# Telemetry_System.net
KiCad netlist of a schematic drawn in Altium Designer
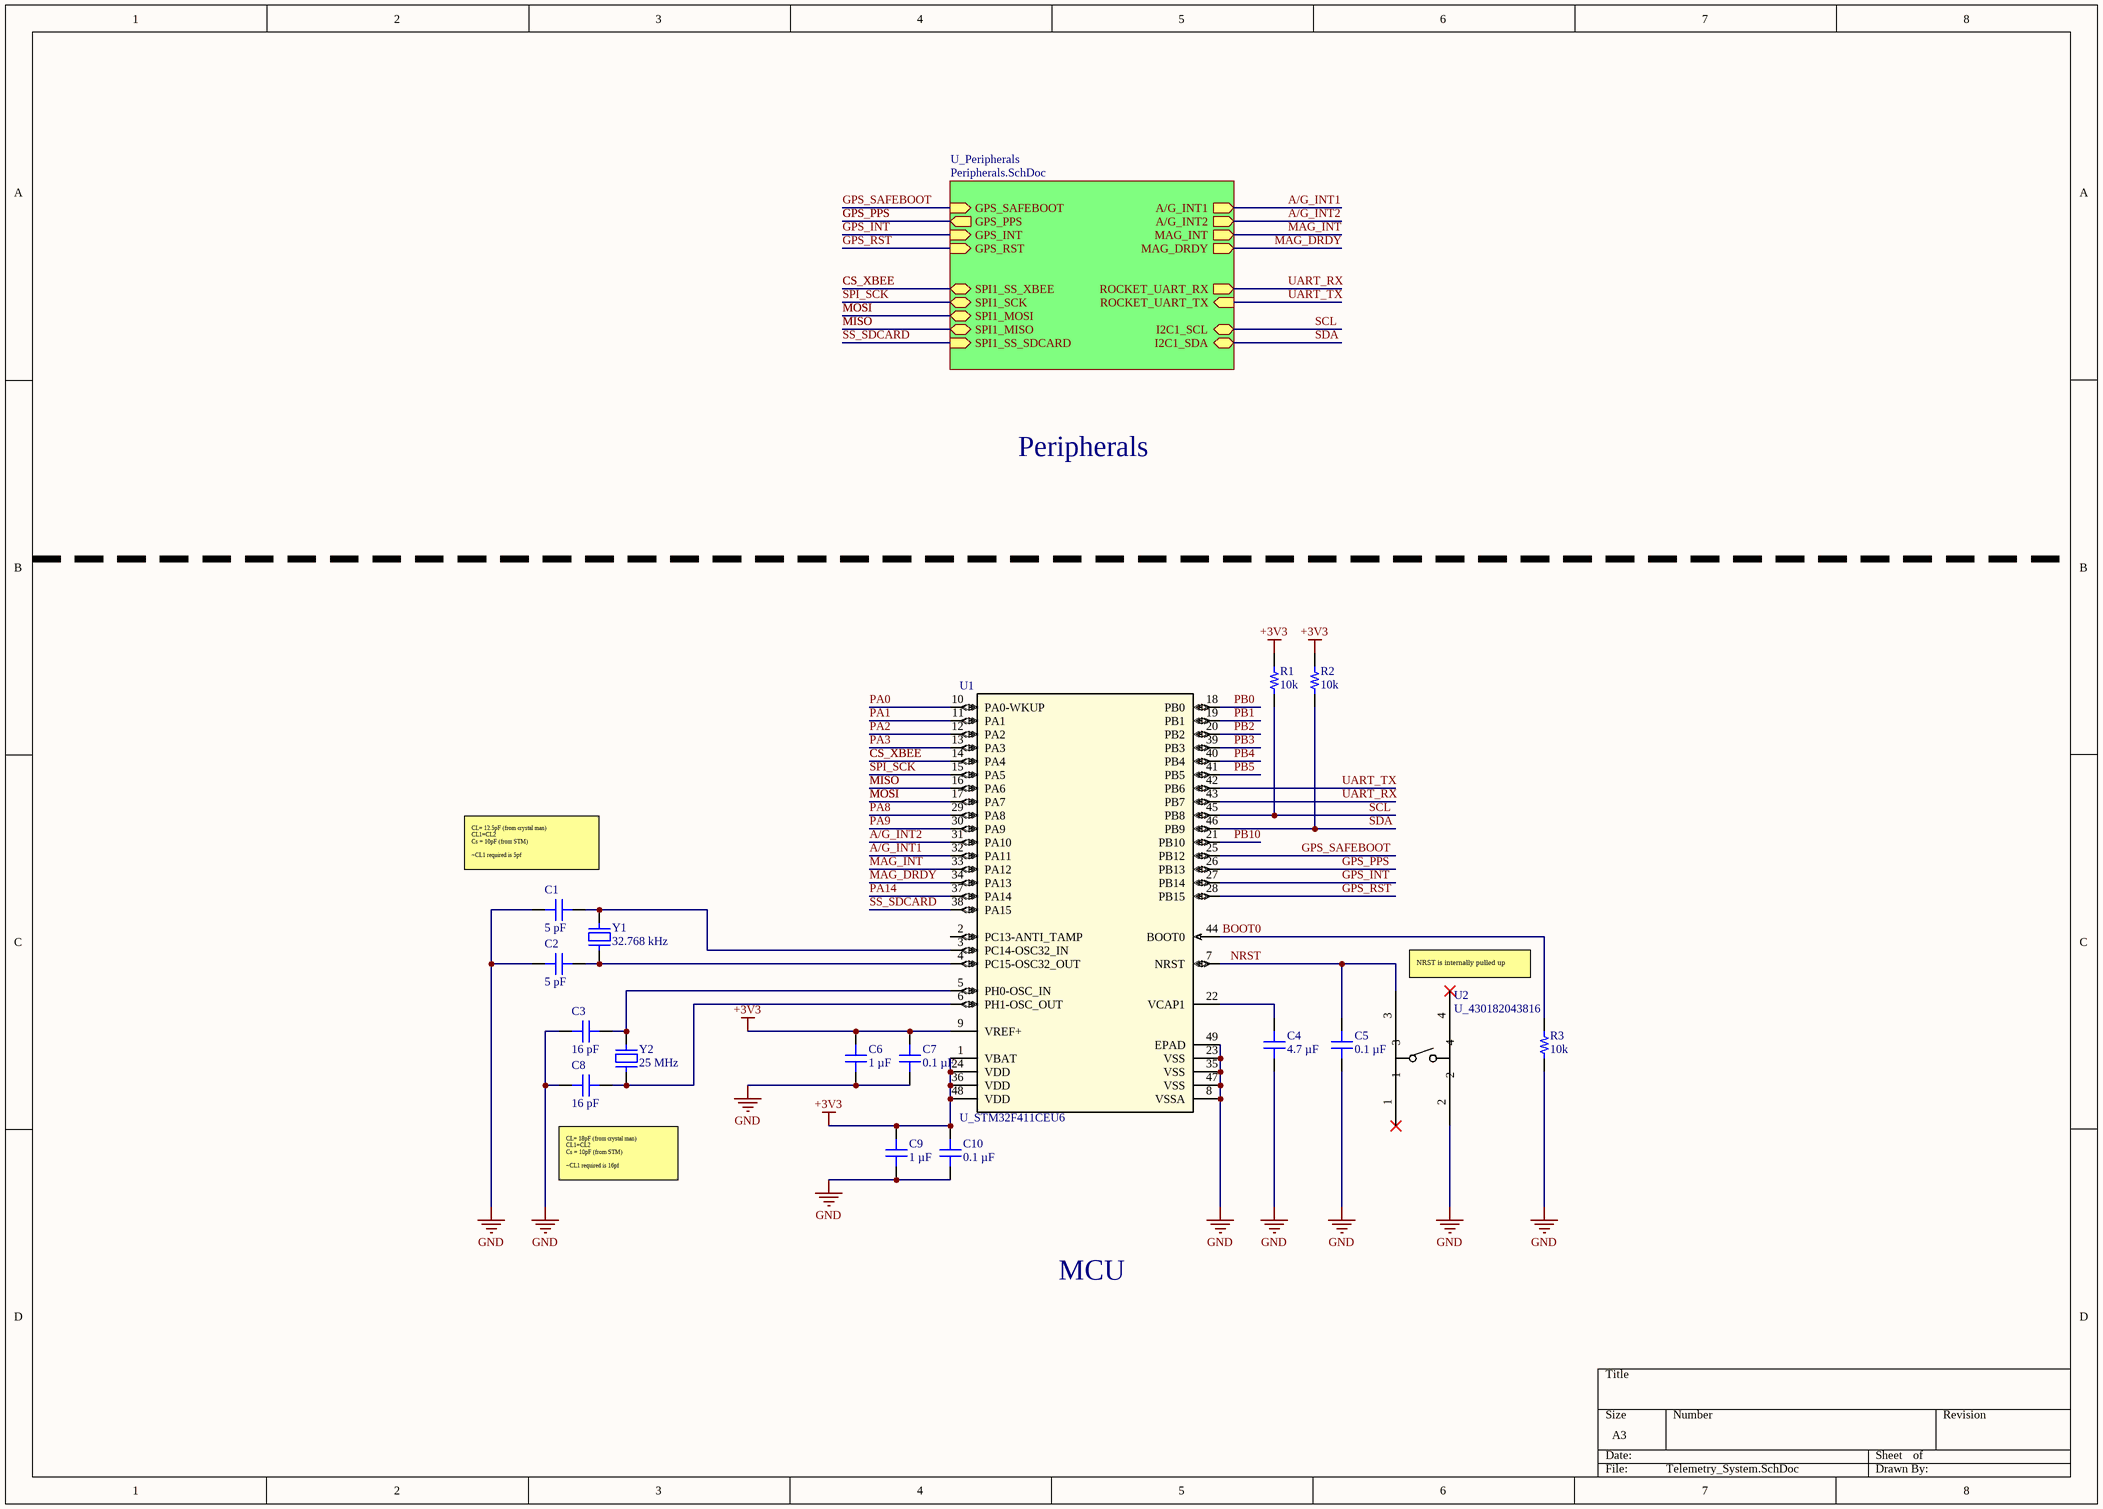
[diagram p0: Telemetry_System.SchDoc]

(export (version "E")
  (design (tool "Eeschema 10.0.6"))
  (components
    (comp (ref "C1")
      (value "5 pF")
      (footprint "CAP 0603_1608")
      (description "CAP CER 5PF 50V 0603 EPOXY")
      (fields
        (field (name "PART NUMBER") "CGA3E2C0G1H050C080AD")
        (field (name "MANUFACTURER") "TDK Corporation")
      )
      (libsource (lib "Celestial Altium Library - altium_library") (part "Capacitor"))
    )
    (comp (ref "C2")
      (value "5 pF")
      (footprint "CAP 0603_1608")
      (description "CAP CER 5PF 50V 0603 EPOXY")
      (fields
        (field (name "PART NUMBER") "CGA3E2C0G1H050C080AD")
        (field (name "MANUFACTURER") "TDK Corporation")
      )
      (libsource (lib "Celestial Altium Library - altium_library") (part "Capacitor"))
    )
    (comp (ref "C3")
      (value "16 pF")
      (footprint "CAP 0603_1608")
      (description "CAP CER 16PF 25V C0G/NP0 0603")
      (fields (field (name "PART NUMBER") "C0603C160K3GAC7867") (field (name "MANUFACTURER") "KEMET"))
      (libsource (lib "Celestial Altium Library - altium_library") (part "Capacitor"))
    )
    (comp (ref "C4")
      (value "4.7 µF")
      (footprint "CAP 0603_1608")
      (description "CAP CER 4.7UF 6.3V X6S 0603")
      (fields
        (field (name "PART NUMBER") "GRM185C80J475ME11D")
        (field (name "MANUFACTURER") "Murata Electronics")
      )
      (libsource (lib "Celestial Altium Library - altium_library") (part "Capacitor"))
    )
    (comp (ref "C5")
      (value "0.1 µF")
      (footprint "CAP 0402_1005")
      (description "CAP CER 100NF 10V X7R 0402")
      (fields
        (field (name "PART NUMBER") "CL05B104KP5VPNC")
        (field (name "MANUFACTURER") "Samsung Electro-Mechanics")
      )
      (libsource (lib "Celestial Altium Library - altium_library") (part "Capacitor"))
    )
    (comp (ref "C6")
      (value "1 µF")
      (footprint "CAP 0402_1005")
      (description "CAP CER 1UF 4V X5R 0402")
      (fields (field (name "PART NUMBER") "KGM05AR50G105KH") (field (name "MANUFACTURER") "KYOCERA AVX"))
      (libsource (lib "Celestial Altium Library - altium_library") (part "Capacitor"))
    )
    (comp (ref "C7")
      (value "0.1 µF")
      (footprint "CAP 0402_1005")
      (description "CAP CER 100NF 10V X7R 0402")
      (fields
        (field (name "PART NUMBER") "CL05B104KP5VPNC")
        (field (name "MANUFACTURER") "Samsung Electro-Mechanics")
      )
      (libsource (lib "Celestial Altium Library - altium_library") (part "Capacitor"))
    )
    (comp (ref "C8")
      (value "16 pF")
      (footprint "CAP 0603_1608")
      (description "CAP CER 16PF 25V C0G/NP0 0603")
      (fields (field (name "PART NUMBER") "C0603C160K3GAC7867") (field (name "MANUFACTURER") "KEMET"))
      (libsource (lib "Celestial Altium Library - altium_library") (part "Capacitor"))
    )
    (comp (ref "C9")
      (value "1 µF")
      (footprint "CAP 0402_1005")
      (description "CAP CER 1UF 4V X5R 0402")
      (fields (field (name "PART NUMBER") "KGM05AR50G105KH") (field (name "MANUFACTURER") "KYOCERA AVX"))
      (libsource (lib "Celestial Altium Library - altium_library") (part "Capacitor"))
    )
    (comp (ref "C10")
      (value "0.1 µF")
      (footprint "CAP 0402_1005")
      (description "CAP CER 100NF 10V X7R 0402")
      (fields
        (field (name "PART NUMBER") "CL05B104KP5VPNC")
        (field (name "MANUFACTURER") "Samsung Electro-Mechanics")
      )
      (libsource (lib "Celestial Altium Library - altium_library") (part "Capacitor"))
    )
    (comp (ref "R1")
      (value "10k")
      (footprint "RES 0402_1005")
      (description "RES 10K OHM 0.1% 1/10W 0402")
      (fields
        (field (name "PART NUMBER") "RP73PF1E10KBTD")
        (field (name "MANUFACTURER") "TE Connectivity Passive Product")
      )
      (libsource (lib "Celestial Altium Library - altium_library") (part "Resistor"))
    )
    (comp (ref "R2")
      (value "10k")
      (footprint "RES 0402_1005")
      (description "RES 10K OHM 0.1% 1/10W 0402")
      (fields
        (field (name "PART NUMBER") "RP73PF1E10KBTD")
        (field (name "MANUFACTURER") "TE Connectivity Passive Product")
      )
      (libsource (lib "Celestial Altium Library - altium_library") (part "Resistor"))
    )
    (comp (ref "R3")
      (value "10k")
      (footprint "RES 0402_1005")
      (description "RES 10K OHM 0.1% 1/10W 0402")
      (fields
        (field (name "PART NUMBER") "RP73PF1E10KBTD")
        (field (name "MANUFACTURER") "TE Connectivity Passive Product")
      )
      (libsource (lib "Celestial Altium Library - altium_library") (part "Resistor"))
    )
    (comp (ref "U1")
      (value "U_STM32F411CEU6")
      (footprint "UFQFPN-48_7X7X0P55MM")
      (description "No Description Available")
      (libsource (lib "U_STM32F411CEU6") (part "U_STM32F411CEU6"))
    )
    (comp (ref "U2")
      (value "U_430182043816")
      (footprint "SOIC_82043816_WRE")
      (description "No Description Available")
      (libsource (lib "U_430182043816") (part "U_430182043816"))
    )
    (comp (ref "Y1")
      (value "32.768 kHz")
      (footprint "MICRO CRYSTAL CM8V H0.6mm")
      (description "CRYSTAL 32.7680KHZ 12.5PF SMD")
      (fields
        (field (name "PART NUMBER") "CM8V-T1A-32.768KHZ-12.5PF-20PPM-TB-QA")
        (field (name "MANUFACTURER") "Micro Crystal AG")
      )
      (libsource (lib "Celestial Altium Library - altium_library") (part "MICRO CRYSTAL CM8V"))
    )
    (comp (ref "Y2")
      (value "25 MHz")
      (footprint "ABRACON ABLS")
      (description "CRYSTAL 25.0000MHZ 18PF SMD")
      (fields (field (name "PART NUMBER") "ABLS-25.000MHZ-K4F-T") (field (name "MANUFACTURER") "Abracon LLC"))
      (libsource (lib "Celestial Altium Library - altium_library") (part "Abracon Crystal ABLS"))
    )
  )
  (nets
    (net (code "1") (name "+3V3") (class "Default")
      (node (ref "C10") (pin "2") (pinfunction "2_2") (pintype "passive"))
      (node (ref "C6") (pin "2") (pinfunction "2_2") (pintype "passive"))
      (node (ref "C7") (pin "2") (pinfunction "2_2") (pintype "passive"))
      (node (ref "C9") (pin "2") (pinfunction "2_2") (pintype "passive"))
      (node (ref "R1") (pin "1") (pinfunction "1_1") (pintype "passive"))
      (node (ref "R2") (pin "1") (pinfunction "1_1") (pintype "passive"))
      (node (ref "U1") (pin "1") (pinfunction "VBAT_1") (pintype "power_in"))
      (node (ref "U1") (pin "24") (pinfunction "VDD_24") (pintype "power_in"))
      (node (ref "U1") (pin "36") (pinfunction "VDD_36") (pintype "power_in"))
      (node (ref "U1") (pin "48") (pinfunction "VDD_48") (pintype "power_in"))
      (node (ref "U1") (pin "9") (pinfunction "VREF+_9") (pintype "power_in"))
    )
    (net (code "2") (name "/A{slash}G_INT1") (class "Default")
      (node (ref "U1") (pin "32") (pinfunction "PA11_32") (pintype "bidirectional"))
    )
    (net (code "3") (name "/A{slash}G_INT2") (class "Default")
      (node (ref "U1") (pin "31") (pinfunction "PA10_31") (pintype "bidirectional"))
    )
    (net (code "4") (name "/BOOT0") (class "Default")
      (node (ref "R3") (pin "1") (pinfunction "1_1") (pintype "passive"))
      (node (ref "U1") (pin "44") (pinfunction "BOOT0_44") (pintype "input"))
    )
    (net (code "5") (name "/CS_XBEE") (class "Default")
      (node (ref "U1") (pin "14") (pinfunction "PA4_14") (pintype "bidirectional"))
    )
    (net (code "6") (name "/GPS_INT") (class "Default")
      (node (ref "U1") (pin "27") (pinfunction "PB14_27") (pintype "bidirectional"))
    )
    (net (code "7") (name "/GPS_PPS") (class "Default")
      (node (ref "U1") (pin "26") (pinfunction "PB13_26") (pintype "bidirectional"))
    )
    (net (code "8") (name "/GPS_RST") (class "Default")
      (node (ref "U1") (pin "28") (pinfunction "PB15_28") (pintype "bidirectional"))
    )
    (net (code "9") (name "/GPS_SAFEBOOT") (class "Default")
      (node (ref "U1") (pin "25") (pinfunction "PB12_25") (pintype "bidirectional"))
    )
    (net (code "10") (name "/MAG_DRDY") (class "Default")
      (node (ref "U1") (pin "34") (pinfunction "PA13_34") (pintype "bidirectional"))
    )
    (net (code "11") (name "/MAG_INT") (class "Default")
      (node (ref "U1") (pin "33") (pinfunction "PA12_33") (pintype "bidirectional"))
    )
    (net (code "12") (name "/MISO") (class "Default")
      (node (ref "U1") (pin "16") (pinfunction "PA6_16") (pintype "bidirectional"))
    )
    (net (code "13") (name "/MOSI") (class "Default")
      (node (ref "U1") (pin "17") (pinfunction "PA7_17") (pintype "bidirectional"))
    )
    (net (code "14") (name "/NRST") (class "Default")
      (node (ref "C5") (pin "2") (pinfunction "2_2") (pintype "passive"))
      (node (ref "U1") (pin "7") (pinfunction "NRST_7") (pintype "bidirectional"))
      (node (ref "U2") (pin "3") (pinfunction "3_3") (pintype "passive"))
    )
    (net (code "15") (name "/PA0") (class "Default")
      (node (ref "U1") (pin "10") (pinfunction "PA0-WKUP_10") (pintype "bidirectional"))
    )
    (net (code "16") (name "/PA1") (class "Default")
      (node (ref "U1") (pin "11") (pinfunction "PA1_11") (pintype "bidirectional"))
    )
    (net (code "17") (name "/PA2") (class "Default")
      (node (ref "U1") (pin "12") (pinfunction "PA2_12") (pintype "bidirectional"))
    )
    (net (code "18") (name "/PA3") (class "Default")
      (node (ref "U1") (pin "13") (pinfunction "PA3_13") (pintype "bidirectional"))
    )
    (net (code "19") (name "/PA8") (class "Default")
      (node (ref "U1") (pin "29") (pinfunction "PA8_29") (pintype "bidirectional"))
    )
    (net (code "20") (name "/PA9") (class "Default")
      (node (ref "U1") (pin "30") (pinfunction "PA9_30") (pintype "bidirectional"))
    )
    (net (code "21") (name "/PA14") (class "Default")
      (node (ref "U1") (pin "37") (pinfunction "PA14_37") (pintype "bidirectional"))
    )
    (net (code "22") (name "/PB0") (class "Default")
      (node (ref "U1") (pin "18") (pinfunction "PB0_18") (pintype "bidirectional"))
    )
    (net (code "23") (name "/PB1") (class "Default")
      (node (ref "U1") (pin "19") (pinfunction "PB1_19") (pintype "bidirectional"))
    )
    (net (code "24") (name "/PB2") (class "Default")
      (node (ref "U1") (pin "20") (pinfunction "PB2_20") (pintype "bidirectional"))
    )
    (net (code "25") (name "/PB3") (class "Default")
      (node (ref "U1") (pin "39") (pinfunction "PB3_39") (pintype "bidirectional"))
    )
    (net (code "26") (name "/PB4") (class "Default")
      (node (ref "U1") (pin "40") (pinfunction "PB4_40") (pintype "bidirectional"))
    )
    (net (code "27") (name "/PB5") (class "Default")
      (node (ref "U1") (pin "41") (pinfunction "PB5_41") (pintype "bidirectional"))
    )
    (net (code "28") (name "/PB10") (class "Default")
      (node (ref "U1") (pin "21") (pinfunction "PB10_21") (pintype "bidirectional"))
    )
    (net (code "29") (name "/SCL") (class "Default")
      (node (ref "R1") (pin "2") (pinfunction "2_2") (pintype "passive"))
      (node (ref "U1") (pin "45") (pinfunction "PB8_45") (pintype "bidirectional"))
    )
    (net (code "30") (name "/SDA") (class "Default")
      (node (ref "R2") (pin "2") (pinfunction "2_2") (pintype "passive"))
      (node (ref "U1") (pin "46") (pinfunction "PB9_46") (pintype "bidirectional"))
    )
    (net (code "31") (name "/SPI_SCK") (class "Default")
      (node (ref "U1") (pin "15") (pinfunction "PA5_15") (pintype "bidirectional"))
    )
    (net (code "32") (name "/SS_SDCARD") (class "Default")
      (node (ref "U1") (pin "38") (pinfunction "PA15_38") (pintype "bidirectional"))
    )
    (net (code "33") (name "/UART_RX") (class "Default")
      (node (ref "U1") (pin "43") (pinfunction "PB7_43") (pintype "bidirectional"))
    )
    (net (code "34") (name "/UART_TX") (class "Default")
      (node (ref "U1") (pin "42") (pinfunction "PB6_42") (pintype "bidirectional"))
    )
    (net (code "35") (name "GND") (class "Default")
      (node (ref "C1") (pin "1") (pinfunction "1_1") (pintype "passive"))
      (node (ref "C10") (pin "1") (pinfunction "1_1") (pintype "passive"))
      (node (ref "C2") (pin "1") (pinfunction "1_1") (pintype "passive"))
      (node (ref "C3") (pin "1") (pinfunction "1_1") (pintype "passive"))
      (node (ref "C4") (pin "1") (pinfunction "1_1") (pintype "passive"))
      (node (ref "C5") (pin "1") (pinfunction "1_1") (pintype "passive"))
      (node (ref "C6") (pin "1") (pinfunction "1_1") (pintype "passive"))
      (node (ref "C7") (pin "1") (pinfunction "1_1") (pintype "passive"))
      (node (ref "C8") (pin "1") (pinfunction "1_1") (pintype "passive"))
      (node (ref "C9") (pin "1") (pinfunction "1_1") (pintype "passive"))
      (node (ref "R3") (pin "2") (pinfunction "2_2") (pintype "passive"))
      (node (ref "U1") (pin "23") (pinfunction "VSS_23") (pintype "power_in"))
      (node (ref "U1") (pin "35") (pinfunction "VSS_35") (pintype "power_in"))
      (node (ref "U1") (pin "47") (pinfunction "VSS_47") (pintype "power_in"))
      (node (ref "U1") (pin "49") (pinfunction "EPAD_49") (pintype "passive"))
      (node (ref "U1") (pin "8") (pinfunction "VSSA_8") (pintype "power_in"))
      (node (ref "U2") (pin "2") (pinfunction "2_2") (pintype "passive"))
    )
    (net (code "36") (name "Net-(U1-PC14-OSC32_IN)") (class "Default")
      (node (ref "C1") (pin "2") (pinfunction "2_2") (pintype "passive"))
      (node (ref "U1") (pin "3") (pinfunction "PC14-OSC32_IN_3") (pintype "bidirectional"))
      (node (ref "Y1") (pin "2") (pinfunction "2_2") (pintype "passive"))
    )
    (net (code "37") (name "Net-(U1-PC15-OSC32_OUT)") (class "Default")
      (node (ref "C2") (pin "2") (pinfunction "2_2") (pintype "passive"))
      (node (ref "U1") (pin "4") (pinfunction "PC15-OSC32_OUT_4") (pintype "bidirectional"))
      (node (ref "Y1") (pin "1") (pinfunction "1_1") (pintype "passive"))
    )
    (net (code "38") (name "Net-(U1-PH0-OSC_IN)") (class "Default")
      (node (ref "C3") (pin "2") (pinfunction "2_2") (pintype "passive"))
      (node (ref "U1") (pin "5") (pinfunction "PH0-OSC_IN_5") (pintype "bidirectional"))
      (node (ref "Y2") (pin "2") (pinfunction "2_2") (pintype "passive"))
    )
    (net (code "39") (name "Net-(U1-PH1-OSC_OUT)") (class "Default")
      (node (ref "C8") (pin "2") (pinfunction "2_2") (pintype "passive"))
      (node (ref "U1") (pin "6") (pinfunction "PH1-OSC_OUT_6") (pintype "bidirectional"))
      (node (ref "Y2") (pin "1") (pinfunction "1_1") (pintype "passive"))
    )
    (net (code "40") (name "Net-(U1-VCAP1)") (class "Default")
      (node (ref "C4") (pin "2") (pinfunction "2_2") (pintype "passive"))
      (node (ref "U1") (pin "22") (pinfunction "VCAP1_22") (pintype "power_in"))
    )
    (net (code "41") (name "unconnected-(U1-PC13-ANTI_TAMP-Pad2)") (class "Default")
      (node (ref "U1") (pin "2") (pinfunction "PC13-ANTI_TAMP_2") (pintype "bidirectional"))
    )
    (net (code "42") (name "unconnected-(U2-Pad1)") (class "Default")
      (node (ref "U2") (pin "1") (pinfunction "1_1") (pintype "passive+no_connect"))
    )
    (net (code "43") (name "unconnected-(U2-Pad4)") (class "Default")
      (node (ref "U2") (pin "4") (pinfunction "4_4") (pintype "passive+no_connect"))
    )
  )
)
